# op_amp_brd.net
KiCad netlist of a schematic drawn in EAGLE
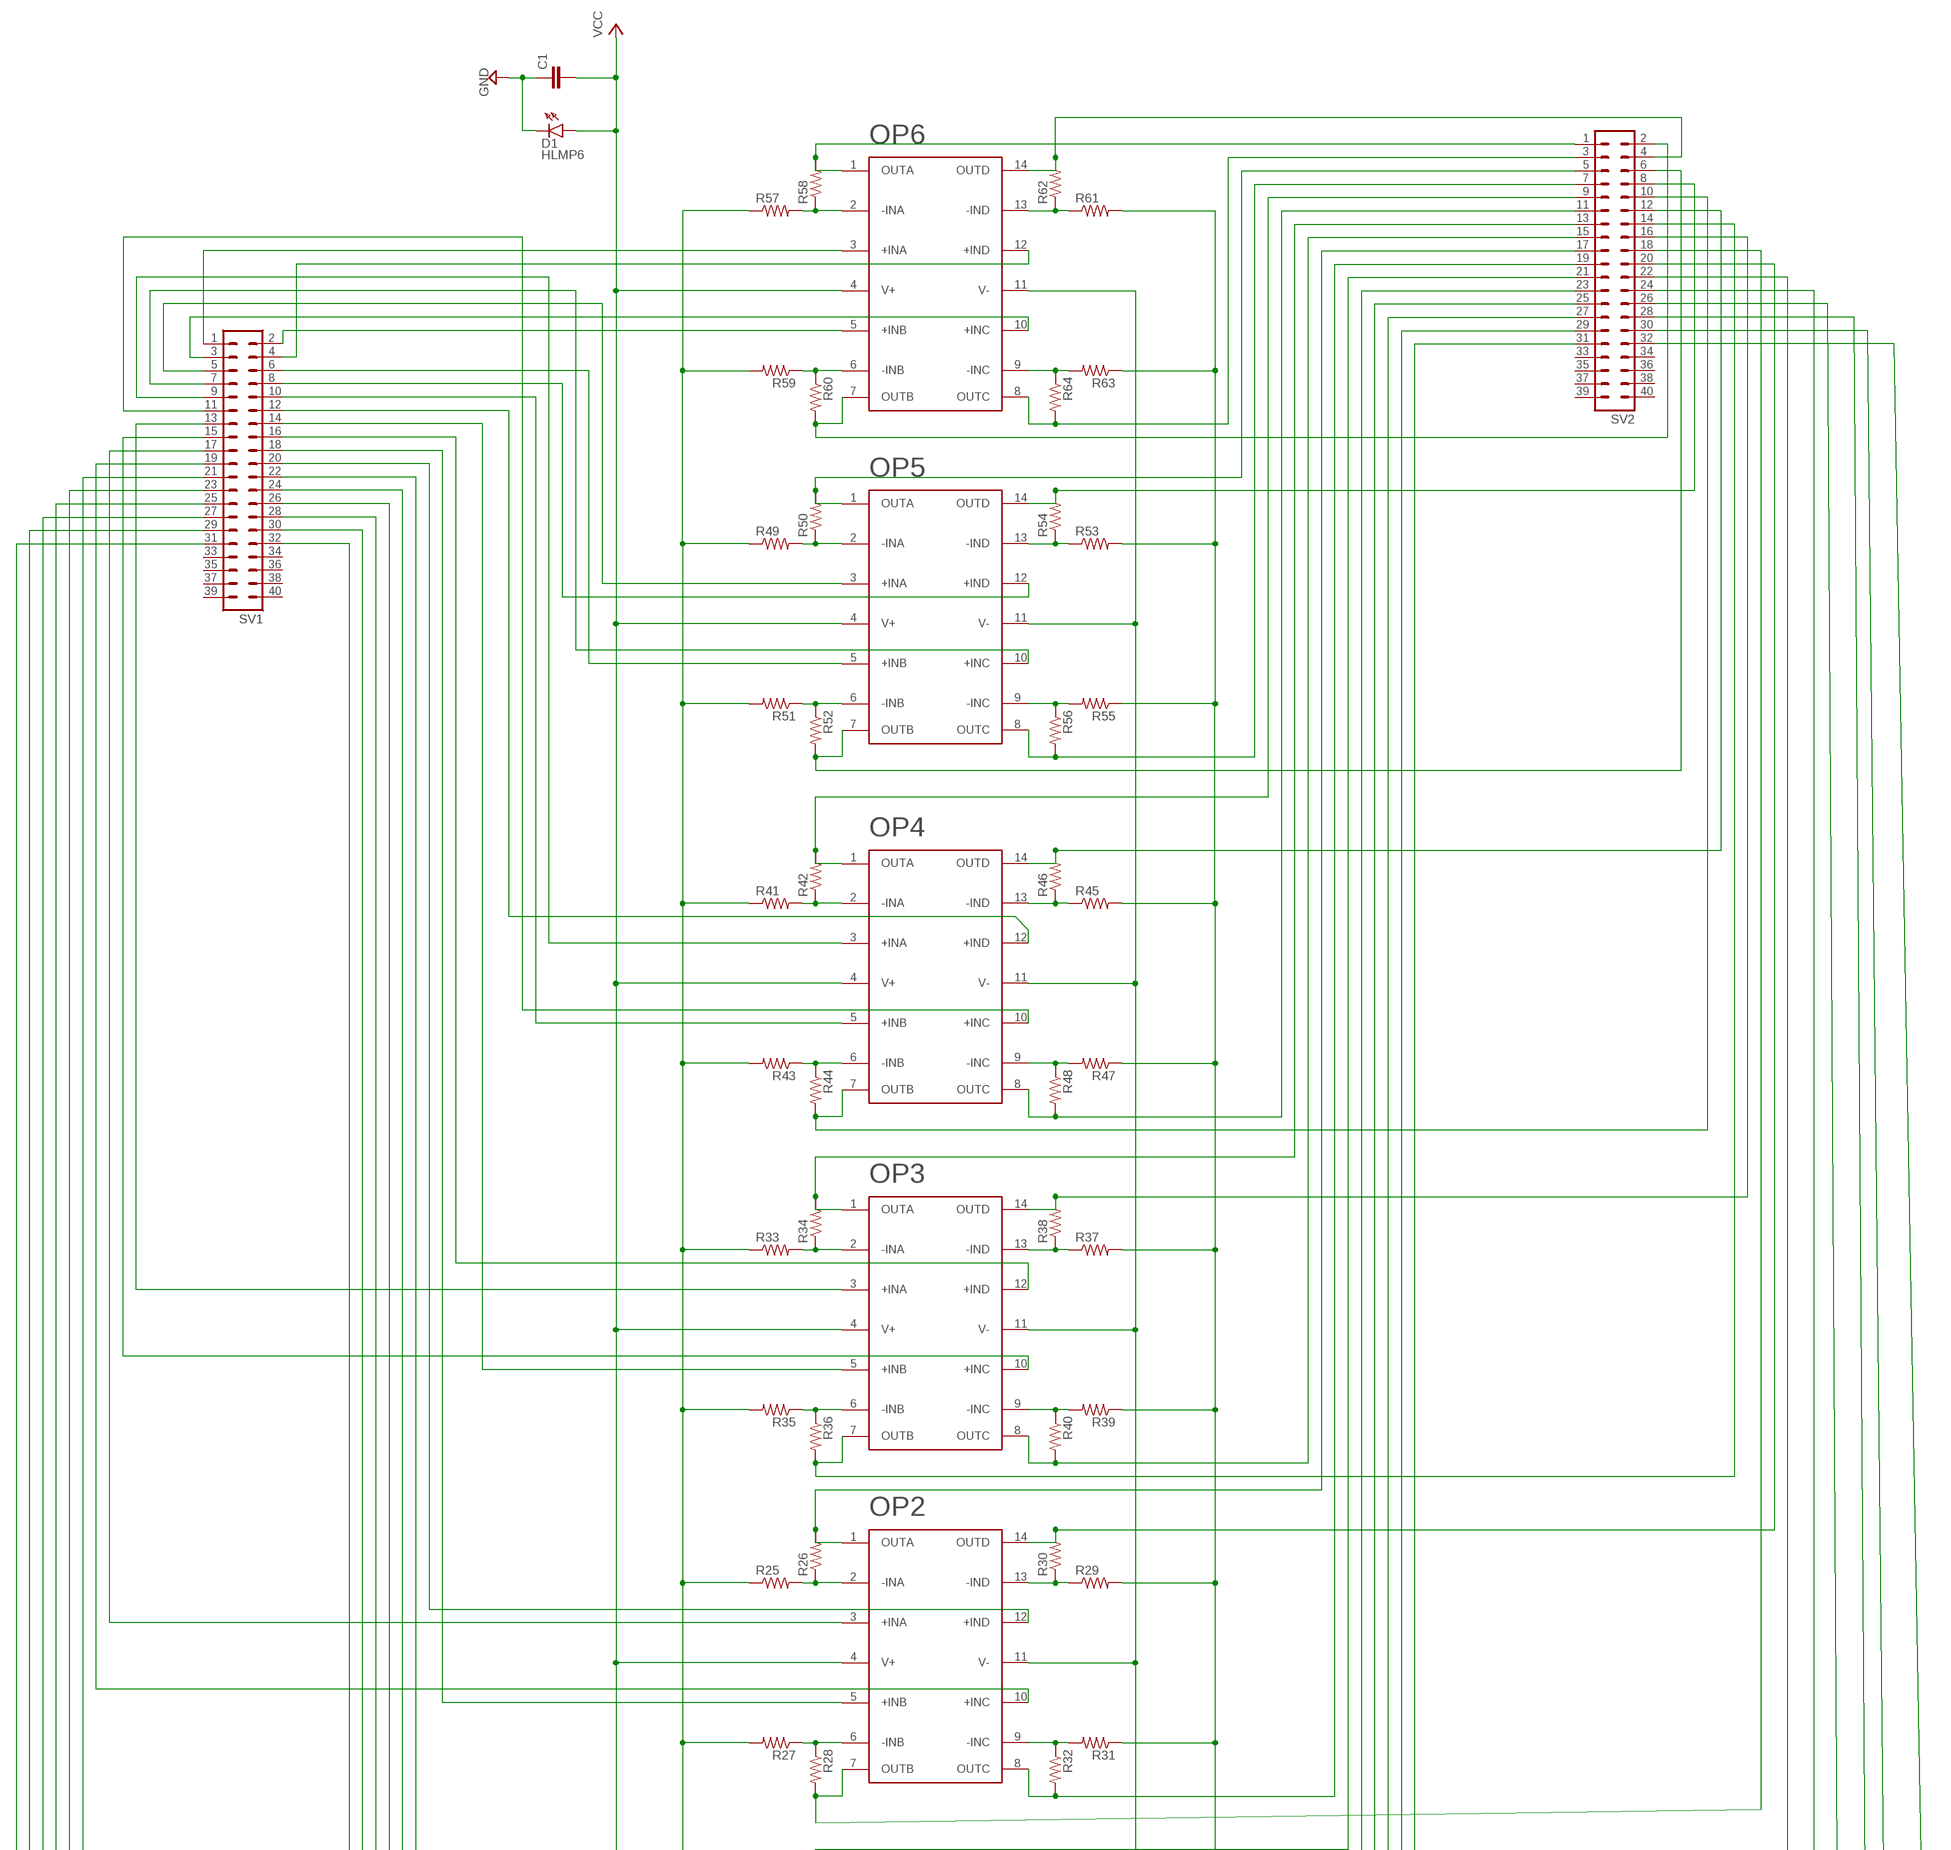
[diagram p0: schematic, sheet 1, part 1 of 2]
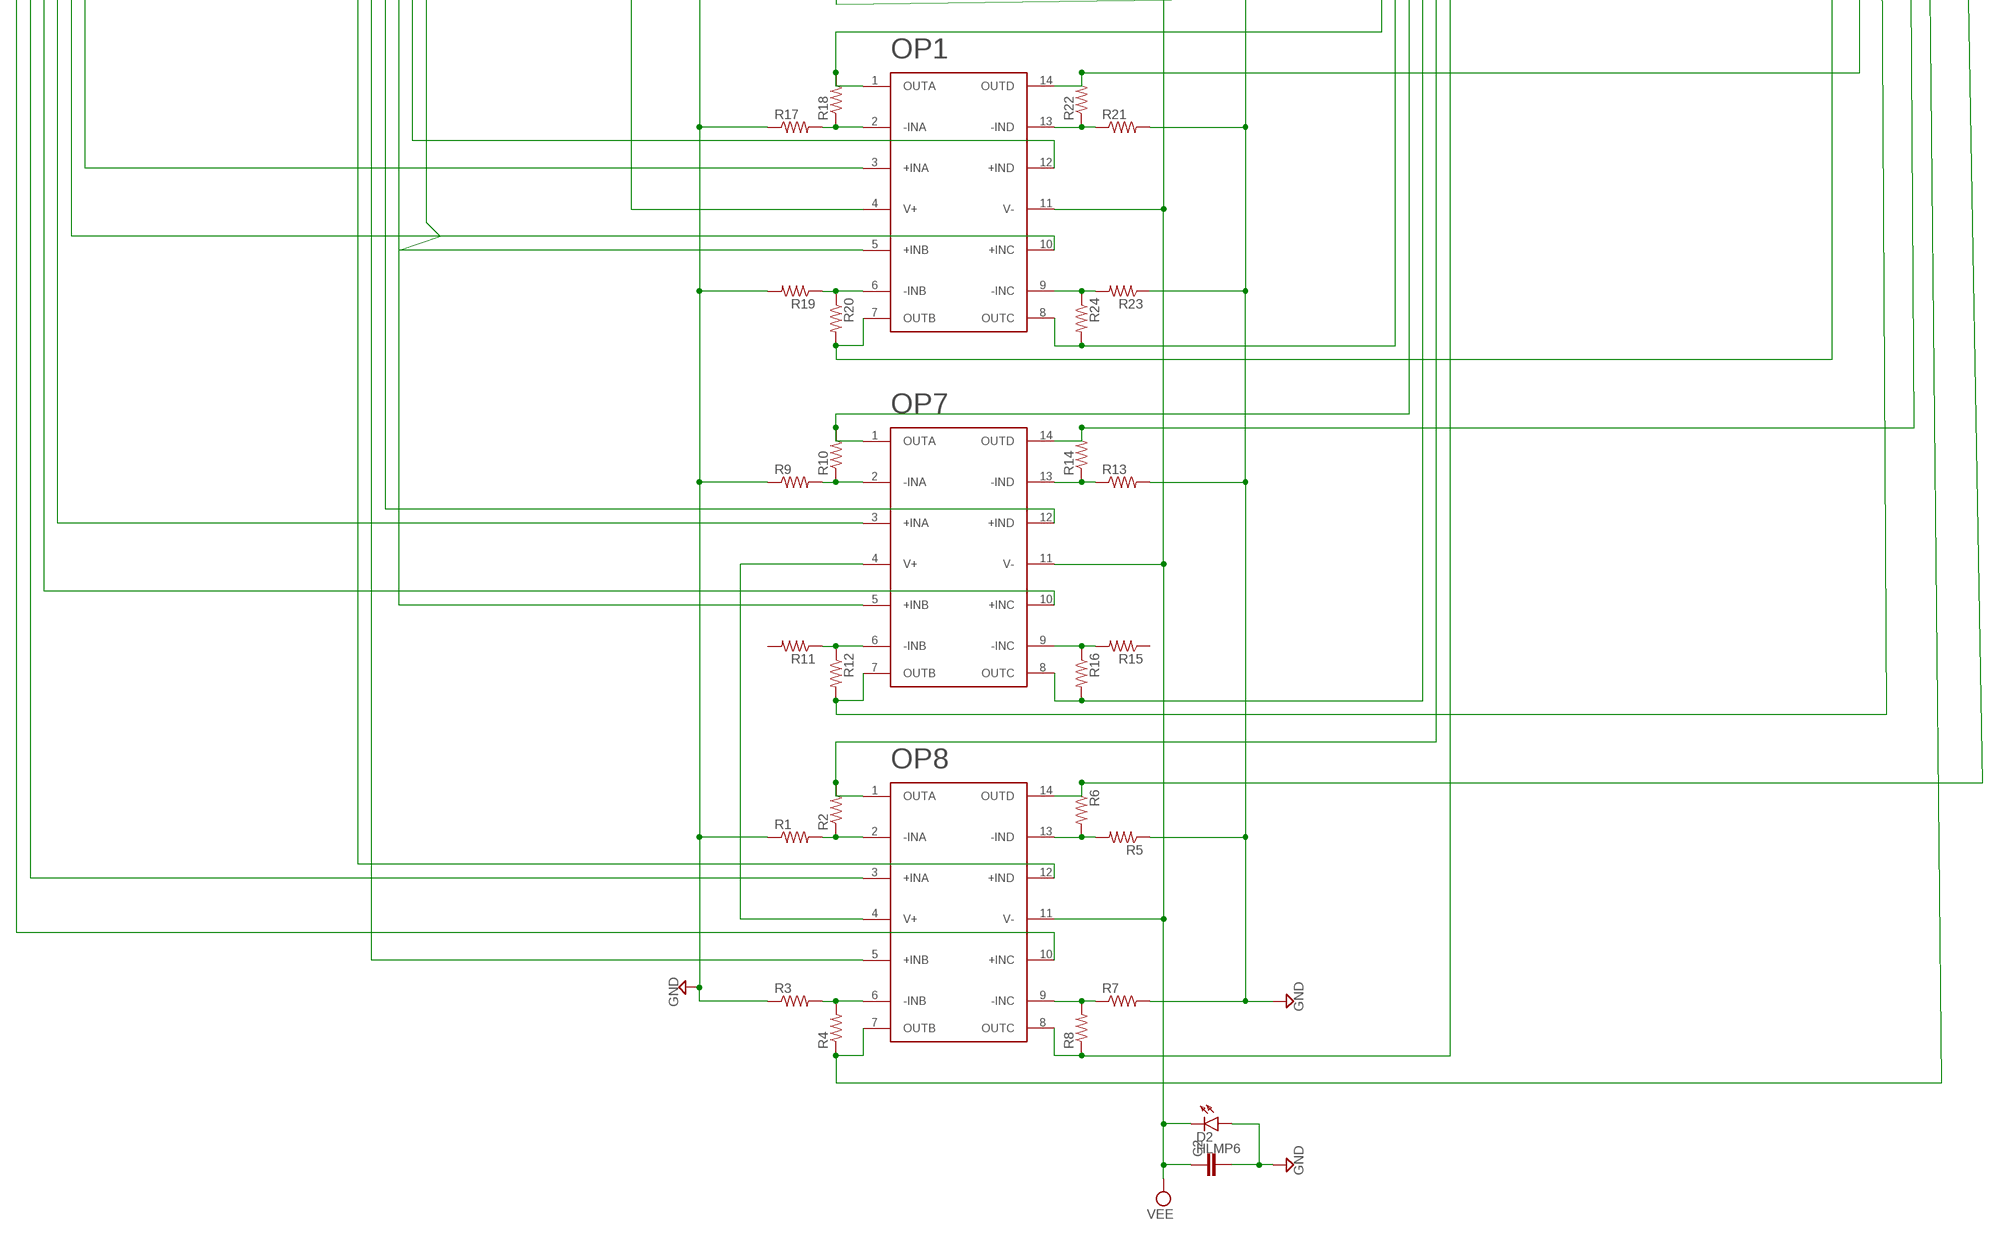
[diagram p1: schematic, sheet 1, part 2 of 2]

(export (version "E")
  (design (tool "Eeschema 10.0.6"))
  (components
    (comp (ref "C1")
      (value "C2,5-3")
      (footprint "eagle-import:C2.5-3")
      (libsource (lib "eagle-import") (part "C2,5-3"))
    )
    (comp (ref "C2")
      (value "C2,5-3")
      (footprint "eagle-import:C2.5-3")
      (libsource (lib "eagle-import") (part "C2,5-3"))
    )
    (comp (ref "D1")
      (value "HLMP6")
      (footprint "eagle-import:HLMP6")
      (fields (field (name "MF") "AGILENT TECHNOLOGIES") (field (name "MPN") "HLMP-6500"))
      (libsource (lib "eagle-import") (part "HLMP6"))
    )
    (comp (ref "D2")
      (value "HLMP6")
      (footprint "eagle-import:HLMP6")
      (fields (field (name "MF") "AGILENT TECHNOLOGIES") (field (name "MPN") "HLMP-6500"))
      (libsource (lib "eagle-import") (part "HLMP6"))
    )
    (comp (ref "OP1")
      (value "OPAX4172")
      (footprint "eagle-import:OPAX172")
      (libsource (lib "eagle-import") (part "OPAX4172"))
    )
    (comp (ref "OP2")
      (value "OPAX4172")
      (footprint "eagle-import:OPAX172")
      (libsource (lib "eagle-import") (part "OPAX4172"))
    )
    (comp (ref "OP3")
      (value "OPAX4172")
      (footprint "eagle-import:OPAX172")
      (libsource (lib "eagle-import") (part "OPAX4172"))
    )
    (comp (ref "OP4")
      (value "OPAX4172")
      (footprint "eagle-import:OPAX172")
      (libsource (lib "eagle-import") (part "OPAX4172"))
    )
    (comp (ref "OP5")
      (value "OPAX4172")
      (footprint "eagle-import:OPAX172")
      (libsource (lib "eagle-import") (part "OPAX4172"))
    )
    (comp (ref "OP6")
      (value "OPAX4172")
      (footprint "eagle-import:OPAX172")
      (libsource (lib "eagle-import") (part "OPAX4172"))
    )
    (comp (ref "OP7")
      (value "OPAX4172")
      (footprint "eagle-import:OPAX172")
      (libsource (lib "eagle-import") (part "OPAX4172"))
    )
    (comp (ref "OP8")
      (value "OPAX4172")
      (footprint "eagle-import:OPAX172")
      (libsource (lib "eagle-import") (part "OPAX4172"))
    )
    (comp (ref "R1")
      (value "R-US_0204/2V")
      (footprint "eagle-import:0204V")
      (libsource (lib "eagle-import") (part "R-US_0204/2V"))
    )
    (comp (ref "R2")
      (value "R-US_0204/2V")
      (footprint "eagle-import:0204V")
      (libsource (lib "eagle-import") (part "R-US_0204/2V"))
    )
    (comp (ref "R3")
      (value "R-US_0204/2V")
      (footprint "eagle-import:0204V")
      (libsource (lib "eagle-import") (part "R-US_0204/2V"))
    )
    (comp (ref "R4")
      (value "R-US_0204/2V")
      (footprint "eagle-import:0204V")
      (libsource (lib "eagle-import") (part "R-US_0204/2V"))
    )
    (comp (ref "R5")
      (value "R-US_0204/2V")
      (footprint "eagle-import:0204V")
      (libsource (lib "eagle-import") (part "R-US_0204/2V"))
    )
    (comp (ref "R6")
      (value "R-US_0204/2V")
      (footprint "eagle-import:0204V")
      (libsource (lib "eagle-import") (part "R-US_0204/2V"))
    )
    (comp (ref "R7")
      (value "R-US_0204/2V")
      (footprint "eagle-import:0204V")
      (libsource (lib "eagle-import") (part "R-US_0204/2V"))
    )
    (comp (ref "R8")
      (value "R-US_0204/2V")
      (footprint "eagle-import:0204V")
      (libsource (lib "eagle-import") (part "R-US_0204/2V"))
    )
    (comp (ref "R9")
      (value "R-US_0204/2V")
      (footprint "eagle-import:0204V")
      (libsource (lib "eagle-import") (part "R-US_0204/2V"))
    )
    (comp (ref "R10")
      (value "R-US_0204/2V")
      (footprint "eagle-import:0204V")
      (libsource (lib "eagle-import") (part "R-US_0204/2V"))
    )
    (comp (ref "R11")
      (value "R-US_0204/2V")
      (footprint "eagle-import:0204V")
      (libsource (lib "eagle-import") (part "R-US_0204/2V"))
    )
    (comp (ref "R12")
      (value "R-US_0204/2V")
      (footprint "eagle-import:0204V")
      (libsource (lib "eagle-import") (part "R-US_0204/2V"))
    )
    (comp (ref "R13")
      (value "R-US_0204/2V")
      (footprint "eagle-import:0204V")
      (libsource (lib "eagle-import") (part "R-US_0204/2V"))
    )
    (comp (ref "R14")
      (value "R-US_0204/2V")
      (footprint "eagle-import:0204V")
      (libsource (lib "eagle-import") (part "R-US_0204/2V"))
    )
    (comp (ref "R15")
      (value "R-US_0204/2V")
      (footprint "eagle-import:0204V")
      (libsource (lib "eagle-import") (part "R-US_0204/2V"))
    )
    (comp (ref "R16")
      (value "R-US_0204/2V")
      (footprint "eagle-import:0204V")
      (libsource (lib "eagle-import") (part "R-US_0204/2V"))
    )
    (comp (ref "R17")
      (value "R-US_0204/2V")
      (footprint "eagle-import:0204V")
      (libsource (lib "eagle-import") (part "R-US_0204/2V"))
    )
    (comp (ref "R18")
      (value "R-US_0204/2V")
      (footprint "eagle-import:0204V")
      (libsource (lib "eagle-import") (part "R-US_0204/2V"))
    )
    (comp (ref "R19")
      (value "R-US_0204/2V")
      (footprint "eagle-import:0204V")
      (libsource (lib "eagle-import") (part "R-US_0204/2V"))
    )
    (comp (ref "R20")
      (value "R-US_0204/2V")
      (footprint "eagle-import:0204V")
      (libsource (lib "eagle-import") (part "R-US_0204/2V"))
    )
    (comp (ref "R21")
      (value "R-US_0204/2V")
      (footprint "eagle-import:0204V")
      (libsource (lib "eagle-import") (part "R-US_0204/2V"))
    )
    (comp (ref "R22")
      (value "R-US_0204/2V")
      (footprint "eagle-import:0204V")
      (libsource (lib "eagle-import") (part "R-US_0204/2V"))
    )
    (comp (ref "R23")
      (value "R-US_0204/2V")
      (footprint "eagle-import:0204V")
      (libsource (lib "eagle-import") (part "R-US_0204/2V"))
    )
    (comp (ref "R24")
      (value "R-US_0204/2V")
      (footprint "eagle-import:0204V")
      (libsource (lib "eagle-import") (part "R-US_0204/2V"))
    )
    (comp (ref "R25")
      (value "R-US_0204/2V")
      (footprint "eagle-import:0204V")
      (libsource (lib "eagle-import") (part "R-US_0204/2V"))
    )
    (comp (ref "R26")
      (value "R-US_0204/2V")
      (footprint "eagle-import:0204V")
      (libsource (lib "eagle-import") (part "R-US_0204/2V"))
    )
    (comp (ref "R27")
      (value "R-US_0204/2V")
      (footprint "eagle-import:0204V")
      (libsource (lib "eagle-import") (part "R-US_0204/2V"))
    )
    (comp (ref "R28")
      (value "R-US_0204/2V")
      (footprint "eagle-import:0204V")
      (libsource (lib "eagle-import") (part "R-US_0204/2V"))
    )
    (comp (ref "R29")
      (value "R-US_0204/2V")
      (footprint "eagle-import:0204V")
      (libsource (lib "eagle-import") (part "R-US_0204/2V"))
    )
    (comp (ref "R30")
      (value "R-US_0204/2V")
      (footprint "eagle-import:0204V")
      (libsource (lib "eagle-import") (part "R-US_0204/2V"))
    )
    (comp (ref "R31")
      (value "R-US_0204/2V")
      (footprint "eagle-import:0204V")
      (libsource (lib "eagle-import") (part "R-US_0204/2V"))
    )
    (comp (ref "R32")
      (value "R-US_0204/2V")
      (footprint "eagle-import:0204V")
      (libsource (lib "eagle-import") (part "R-US_0204/2V"))
    )
    (comp (ref "R33")
      (value "R-US_0204/2V")
      (footprint "eagle-import:0204V")
      (libsource (lib "eagle-import") (part "R-US_0204/2V"))
    )
    (comp (ref "R34")
      (value "R-US_0204/2V")
      (footprint "eagle-import:0204V")
      (libsource (lib "eagle-import") (part "R-US_0204/2V"))
    )
    (comp (ref "R35")
      (value "R-US_0204/2V")
      (footprint "eagle-import:0204V")
      (libsource (lib "eagle-import") (part "R-US_0204/2V"))
    )
    (comp (ref "R36")
      (value "R-US_0204/2V")
      (footprint "eagle-import:0204V")
      (libsource (lib "eagle-import") (part "R-US_0204/2V"))
    )
    (comp (ref "R37")
      (value "R-US_0204/2V")
      (footprint "eagle-import:0204V")
      (libsource (lib "eagle-import") (part "R-US_0204/2V"))
    )
    (comp (ref "R38")
      (value "R-US_0204/2V")
      (footprint "eagle-import:0204V")
      (libsource (lib "eagle-import") (part "R-US_0204/2V"))
    )
    (comp (ref "R39")
      (value "R-US_0204/2V")
      (footprint "eagle-import:0204V")
      (libsource (lib "eagle-import") (part "R-US_0204/2V"))
    )
    (comp (ref "R40")
      (value "R-US_0204/2V")
      (footprint "eagle-import:0204V")
      (libsource (lib "eagle-import") (part "R-US_0204/2V"))
    )
    (comp (ref "R41")
      (value "R-US_0204/2V")
      (footprint "eagle-import:0204V")
      (libsource (lib "eagle-import") (part "R-US_0204/2V"))
    )
    (comp (ref "R42")
      (value "R-US_0204/2V")
      (footprint "eagle-import:0204V")
      (libsource (lib "eagle-import") (part "R-US_0204/2V"))
    )
    (comp (ref "R43")
      (value "R-US_0204/2V")
      (footprint "eagle-import:0204V")
      (libsource (lib "eagle-import") (part "R-US_0204/2V"))
    )
    (comp (ref "R44")
      (value "R-US_0204/2V")
      (footprint "eagle-import:0204V")
      (libsource (lib "eagle-import") (part "R-US_0204/2V"))
    )
    (comp (ref "R45")
      (value "R-US_0204/2V")
      (footprint "eagle-import:0204V")
      (libsource (lib "eagle-import") (part "R-US_0204/2V"))
    )
    (comp (ref "R46")
      (value "R-US_0204/2V")
      (footprint "eagle-import:0204V")
      (libsource (lib "eagle-import") (part "R-US_0204/2V"))
    )
    (comp (ref "R47")
      (value "R-US_0204/2V")
      (footprint "eagle-import:0204V")
      (libsource (lib "eagle-import") (part "R-US_0204/2V"))
    )
    (comp (ref "R48")
      (value "R-US_0204/2V")
      (footprint "eagle-import:0204V")
      (libsource (lib "eagle-import") (part "R-US_0204/2V"))
    )
    (comp (ref "R49")
      (value "R-US_0204/2V")
      (footprint "eagle-import:0204V")
      (libsource (lib "eagle-import") (part "R-US_0204/2V"))
    )
    (comp (ref "R50")
      (value "R-US_0204/2V")
      (footprint "eagle-import:0204V")
      (libsource (lib "eagle-import") (part "R-US_0204/2V"))
    )
    (comp (ref "R51")
      (value "R-US_0204/2V")
      (footprint "eagle-import:0204V")
      (libsource (lib "eagle-import") (part "R-US_0204/2V"))
    )
    (comp (ref "R52")
      (value "R-US_0204/2V")
      (footprint "eagle-import:0204V")
      (libsource (lib "eagle-import") (part "R-US_0204/2V"))
    )
    (comp (ref "R53")
      (value "R-US_0204/2V")
      (footprint "eagle-import:0204V")
      (libsource (lib "eagle-import") (part "R-US_0204/2V"))
    )
    (comp (ref "R54")
      (value "R-US_0204/2V")
      (footprint "eagle-import:0204V")
      (libsource (lib "eagle-import") (part "R-US_0204/2V"))
    )
    (comp (ref "R55")
      (value "R-US_0204/2V")
      (footprint "eagle-import:0204V")
      (libsource (lib "eagle-import") (part "R-US_0204/2V"))
    )
    (comp (ref "R56")
      (value "R-US_0204/2V")
      (footprint "eagle-import:0204V")
      (libsource (lib "eagle-import") (part "R-US_0204/2V"))
    )
    (comp (ref "R57")
      (value "R-US_0204/2V")
      (footprint "eagle-import:0204V")
      (libsource (lib "eagle-import") (part "R-US_0204/2V"))
    )
    (comp (ref "R58")
      (value "R-US_0204/2V")
      (footprint "eagle-import:0204V")
      (libsource (lib "eagle-import") (part "R-US_0204/2V"))
    )
    (comp (ref "R59")
      (value "R-US_0204/2V")
      (footprint "eagle-import:0204V")
      (libsource (lib "eagle-import") (part "R-US_0204/2V"))
    )
    (comp (ref "R60")
      (value "R-US_0204/2V")
      (footprint "eagle-import:0204V")
      (libsource (lib "eagle-import") (part "R-US_0204/2V"))
    )
    (comp (ref "R61")
      (value "R-US_0204/2V")
      (footprint "eagle-import:0204V")
      (libsource (lib "eagle-import") (part "R-US_0204/2V"))
    )
    (comp (ref "R62")
      (value "R-US_0204/2V")
      (footprint "eagle-import:0204V")
      (libsource (lib "eagle-import") (part "R-US_0204/2V"))
    )
    (comp (ref "R63")
      (value "R-US_0204/2V")
      (footprint "eagle-import:0204V")
      (libsource (lib "eagle-import") (part "R-US_0204/2V"))
    )
    (comp (ref "R64")
      (value "R-US_0204/2V")
      (footprint "eagle-import:0204V")
      (libsource (lib "eagle-import") (part "R-US_0204/2V"))
    )
    (comp (ref "SV1")
      (value "MA20-2")
      (footprint "eagle-import:MA20-2")
      (libsource (lib "eagle-import") (part "MA20-2"))
    )
    (comp (ref "SV2")
      (value "MA20-2W")
      (footprint "eagle-import:MA20-2W")
      (libsource (lib "eagle-import") (part "MA20-2W"))
    )
  )
  (nets
    (net (code "1") (name "GND") (class "Default")
      (node (ref "C1") (pin "1") (pinfunction "1_1") (pintype "passive"))
      (node (ref "C2") (pin "2") (pinfunction "2_2") (pintype "passive"))
      (node (ref "D1") (pin "K") (pinfunction "K_K") (pintype "passive"))
      (node (ref "D2") (pin "A") (pinfunction "A_A") (pintype "passive"))
      (node (ref "R1") (pin "1") (pinfunction "1_1") (pintype "passive"))
      (node (ref "R13") (pin "2") (pinfunction "2_2") (pintype "passive"))
      (node (ref "R17") (pin "1") (pinfunction "1_1") (pintype "passive"))
      (node (ref "R19") (pin "2") (pinfunction "2_2") (pintype "passive"))
      (node (ref "R21") (pin "2") (pinfunction "2_2") (pintype "passive"))
      (node (ref "R23") (pin "1") (pinfunction "1_1") (pintype "passive"))
      (node (ref "R25") (pin "1") (pinfunction "1_1") (pintype "passive"))
      (node (ref "R27") (pin "2") (pinfunction "2_2") (pintype "passive"))
      (node (ref "R29") (pin "2") (pinfunction "2_2") (pintype "passive"))
      (node (ref "R3") (pin "1") (pinfunction "1_1") (pintype "passive"))
      (node (ref "R31") (pin "1") (pinfunction "1_1") (pintype "passive"))
      (node (ref "R33") (pin "1") (pinfunction "1_1") (pintype "passive"))
      (node (ref "R35") (pin "2") (pinfunction "2_2") (pintype "passive"))
      (node (ref "R37") (pin "2") (pinfunction "2_2") (pintype "passive"))
      (node (ref "R39") (pin "1") (pinfunction "1_1") (pintype "passive"))
      (node (ref "R41") (pin "1") (pinfunction "1_1") (pintype "passive"))
      (node (ref "R43") (pin "2") (pinfunction "2_2") (pintype "passive"))
      (node (ref "R45") (pin "2") (pinfunction "2_2") (pintype "passive"))
      (node (ref "R47") (pin "1") (pinfunction "1_1") (pintype "passive"))
      (node (ref "R49") (pin "1") (pinfunction "1_1") (pintype "passive"))
      (node (ref "R5") (pin "1") (pinfunction "1_1") (pintype "passive"))
      (node (ref "R51") (pin "2") (pinfunction "2_2") (pintype "passive"))
      (node (ref "R53") (pin "2") (pinfunction "2_2") (pintype "passive"))
      (node (ref "R55") (pin "1") (pinfunction "1_1") (pintype "passive"))
      (node (ref "R57") (pin "1") (pinfunction "1_1") (pintype "passive"))
      (node (ref "R59") (pin "2") (pinfunction "2_2") (pintype "passive"))
      (node (ref "R61") (pin "2") (pinfunction "2_2") (pintype "passive"))
      (node (ref "R63") (pin "1") (pinfunction "1_1") (pintype "passive"))
      (node (ref "R7") (pin "2") (pinfunction "2_2") (pintype "passive"))
      (node (ref "R9") (pin "1") (pinfunction "1_1") (pintype "passive"))
    )
    (net (code "2") (name "Net-(OP1-+INA)") (class "Default")
      (node (ref "OP1") (pin "3") (pinfunction "+INA_3") (pintype "bidirectional"))
      (node (ref "SV1") (pin "21") (pinfunction "21_21") (pintype "passive"))
    )
    (net (code "3") (name "Net-(OP1-+INB)") (class "Default")
      (node (ref "OP1") (pin "5") (pinfunction "+INB_5") (pintype "bidirectional"))
      (node (ref "SV1") (pin "22") (pinfunction "22_22") (pintype "passive"))
    )
    (net (code "4") (name "Net-(OP1-+INC)") (class "Default")
      (node (ref "OP1") (pin "10") (pinfunction "+INC_10") (pintype "bidirectional"))
      (node (ref "SV1") (pin "23") (pinfunction "23_23") (pintype "passive"))
    )
    (net (code "5") (name "Net-(OP1-+IND)") (class "Default")
      (node (ref "OP1") (pin "12") (pinfunction "+IND_12") (pintype "bidirectional"))
      (node (ref "SV1") (pin "24") (pinfunction "24_24") (pintype "passive"))
    )
    (net (code "6") (name "Net-(OP1--INA)") (class "Default")
      (node (ref "OP1") (pin "2") (pinfunction "-INA_2") (pintype "bidirectional"))
      (node (ref "R17") (pin "2") (pinfunction "2_2") (pintype "passive"))
      (node (ref "R18") (pin "1") (pinfunction "1_1") (pintype "passive"))
    )
    (net (code "7") (name "Net-(OP1--INB)") (class "Default")
      (node (ref "OP1") (pin "6") (pinfunction "-INB_6") (pintype "bidirectional"))
      (node (ref "R19") (pin "1") (pinfunction "1_1") (pintype "passive"))
      (node (ref "R20") (pin "1") (pinfunction "1_1") (pintype "passive"))
    )
    (net (code "8") (name "Net-(OP1--INC)") (class "Default")
      (node (ref "OP1") (pin "9") (pinfunction "-INC_9") (pintype "bidirectional"))
      (node (ref "R23") (pin "2") (pinfunction "2_2") (pintype "passive"))
      (node (ref "R24") (pin "1") (pinfunction "1_1") (pintype "passive"))
    )
    (net (code "9") (name "Net-(OP1--IND)") (class "Default")
      (node (ref "OP1") (pin "13") (pinfunction "-IND_13") (pintype "bidirectional"))
      (node (ref "R21") (pin "1") (pinfunction "1_1") (pintype "passive"))
      (node (ref "R22") (pin "1") (pinfunction "1_1") (pintype "passive"))
    )
    (net (code "10") (name "Net-(OP1-OUTA)") (class "Default")
      (node (ref "OP1") (pin "1") (pinfunction "OUTA_1") (pintype "bidirectional"))
      (node (ref "R18") (pin "2") (pinfunction "2_2") (pintype "passive"))
      (node (ref "SV2") (pin "21") (pinfunction "21_21") (pintype "passive"))
    )
    (net (code "11") (name "Net-(OP1-OUTB)") (class "Default")
      (node (ref "OP1") (pin "7") (pinfunction "OUTB_7") (pintype "bidirectional"))
      (node (ref "R20") (pin "2") (pinfunction "2_2") (pintype "passive"))
      (node (ref "SV2") (pin "22") (pinfunction "22_22") (pintype "passive"))
    )
    (net (code "12") (name "Net-(OP1-OUTC)") (class "Default")
      (node (ref "OP1") (pin "8") (pinfunction "OUTC_8") (pintype "bidirectional"))
      (node (ref "R24") (pin "2") (pinfunction "2_2") (pintype "passive"))
      (node (ref "SV2") (pin "23") (pinfunction "23_23") (pintype "passive"))
    )
    (net (code "13") (name "Net-(OP1-OUTD)") (class "Default")
      (node (ref "OP1") (pin "14") (pinfunction "OUTD_14") (pintype "bidirectional"))
      (node (ref "R22") (pin "2") (pinfunction "2_2") (pintype "passive"))
      (node (ref "SV2") (pin "24") (pinfunction "24_24") (pintype "passive"))
    )
    (net (code "14") (name "Net-(OP2-+INA)") (class "Default")
      (node (ref "OP2") (pin "3") (pinfunction "+INA_3") (pintype "bidirectional"))
      (node (ref "SV1") (pin "17") (pinfunction "17_17") (pintype "passive"))
    )
    (net (code "15") (name "Net-(OP2-+INB)") (class "Default")
      (node (ref "OP2") (pin "5") (pinfunction "+INB_5") (pintype "bidirectional"))
      (node (ref "SV1") (pin "18") (pinfunction "18_18") (pintype "passive"))
    )
    (net (code "16") (name "Net-(OP2-+INC)") (class "Default")
      (node (ref "OP2") (pin "10") (pinfunction "+INC_10") (pintype "bidirectional"))
      (node (ref "SV1") (pin "19") (pinfunction "19_19") (pintype "passive"))
    )
    (net (code "17") (name "Net-(OP2-+IND)") (class "Default")
      (node (ref "OP2") (pin "12") (pinfunction "+IND_12") (pintype "bidirectional"))
      (node (ref "SV1") (pin "20") (pinfunction "20_20") (pintype "passive"))
    )
    (net (code "18") (name "Net-(OP2--INA)") (class "Default")
      (node (ref "OP2") (pin "2") (pinfunction "-INA_2") (pintype "bidirectional"))
      (node (ref "R25") (pin "2") (pinfunction "2_2") (pintype "passive"))
      (node (ref "R26") (pin "1") (pinfunction "1_1") (pintype "passive"))
    )
    (net (code "19") (name "Net-(OP2--INB)") (class "Default")
      (node (ref "OP2") (pin "6") (pinfunction "-INB_6") (pintype "bidirectional"))
      (node (ref "R27") (pin "1") (pinfunction "1_1") (pintype "passive"))
      (node (ref "R28") (pin "1") (pinfunction "1_1") (pintype "passive"))
    )
    (net (code "20") (name "Net-(OP2--INC)") (class "Default")
      (node (ref "OP2") (pin "9") (pinfunction "-INC_9") (pintype "bidirectional"))
      (node (ref "R31") (pin "2") (pinfunction "2_2") (pintype "passive"))
      (node (ref "R32") (pin "1") (pinfunction "1_1") (pintype "passive"))
    )
    (net (code "21") (name "Net-(OP2--IND)") (class "Default")
      (node (ref "OP2") (pin "13") (pinfunction "-IND_13") (pintype "bidirectional"))
      (node (ref "R29") (pin "1") (pinfunction "1_1") (pintype "passive"))
      (node (ref "R30") (pin "1") (pinfunction "1_1") (pintype "passive"))
    )
    (net (code "22") (name "Net-(OP2-OUTA)") (class "Default")
      (node (ref "OP2") (pin "1") (pinfunction "OUTA_1") (pintype "bidirectional"))
      (node (ref "R26") (pin "2") (pinfunction "2_2") (pintype "passive"))
      (node (ref "SV2") (pin "17") (pinfunction "17_17") (pintype "passive"))
    )
    (net (code "23") (name "Net-(OP2-OUTB)") (class "Default")
      (node (ref "OP2") (pin "7") (pinfunction "OUTB_7") (pintype "bidirectional"))
      (node (ref "R28") (pin "2") (pinfunction "2_2") (pintype "passive"))
      (node (ref "SV2") (pin "18") (pinfunction "18_18") (pintype "passive"))
    )
    (net (code "24") (name "Net-(OP2-OUTC)") (class "Default")
      (node (ref "OP2") (pin "8") (pinfunction "OUTC_8") (pintype "bidirectional"))
      (node (ref "R32") (pin "2") (pinfunction "2_2") (pintype "passive"))
      (node (ref "SV2") (pin "19") (pinfunction "19_19") (pintype "passive"))
    )
    (net (code "25") (name "Net-(OP2-OUTD)") (class "Default")
      (node (ref "OP2") (pin "14") (pinfunction "OUTD_14") (pintype "bidirectional"))
      (node (ref "R30") (pin "2") (pinfunction "2_2") (pintype "passive"))
      (node (ref "SV2") (pin "20") (pinfunction "20_20") (pintype "passive"))
    )
    (net (code "26") (name "Net-(OP3-+INA)") (class "Default")
      (node (ref "OP3") (pin "3") (pinfunction "+INA_3") (pintype "bidirectional"))
      (node (ref "SV1") (pin "13") (pinfunction "13_13") (pintype "passive"))
    )
    (net (code "27") (name "Net-(OP3-+INB)") (class "Default")
      (node (ref "OP3") (pin "5") (pinfunction "+INB_5") (pintype "bidirectional"))
      (node (ref "SV1") (pin "14") (pinfunction "14_14") (pintype "passive"))
    )
    (net (code "28") (name "Net-(OP3-+INC)") (class "Default")
      (node (ref "OP3") (pin "10") (pinfunction "+INC_10") (pintype "bidirectional"))
      (node (ref "SV1") (pin "15") (pinfunction "15_15") (pintype "passive"))
    )
    (net (code "29") (name "Net-(OP3-+IND)") (class "Default")
      (node (ref "OP3") (pin "12") (pinfunction "+IND_12") (pintype "bidirectional"))
      (node (ref "SV1") (pin "16") (pinfunction "16_16") (pintype "passive"))
    )
    (net (code "30") (name "Net-(OP3--INA)") (class "Default")
      (node (ref "OP3") (pin "2") (pinfunction "-INA_2") (pintype "bidirectional"))
      (node (ref "R33") (pin "2") (pinfunction "2_2") (pintype "passive"))
      (node (ref "R34") (pin "1") (pinfunction "1_1") (pintype "passive"))
    )
    (net (code "31") (name "Net-(OP3--INB)") (class "Default")
      (node (ref "OP3") (pin "6") (pinfunction "-INB_6") (pintype "bidirectional"))
      (node (ref "R35") (pin "1") (pinfunction "1_1") (pintype "passive"))
      (node (ref "R36") (pin "1") (pinfunction "1_1") (pintype "passive"))
    )
    (net (code "32") (name "Net-(OP3--INC)") (class "Default")
      (node (ref "OP3") (pin "9") (pinfunction "-INC_9") (pintype "bidirectional"))
      (node (ref "R39") (pin "2") (pinfunction "2_2") (pintype "passive"))
      (node (ref "R40") (pin "1") (pinfunction "1_1") (pintype "passive"))
    )
    (net (code "33") (name "Net-(OP3--IND)") (class "Default")
      (node (ref "OP3") (pin "13") (pinfunction "-IND_13") (pintype "bidirectional"))
      (node (ref "R37") (pin "1") (pinfunction "1_1") (pintype "passive"))
      (node (ref "R38") (pin "1") (pinfunction "1_1") (pintype "passive"))
    )
    (net (code "34") (name "Net-(OP3-OUTA)") (class "Default")
      (node (ref "OP3") (pin "1") (pinfunction "OUTA_1") (pintype "bidirectional"))
      (node (ref "R34") (pin "2") (pinfunction "2_2") (pintype "passive"))
      (node (ref "SV2") (pin "13") (pinfunction "13_13") (pintype "passive"))
    )
    (net (code "35") (name "Net-(OP3-OUTB)") (class "Default")
      (node (ref "OP3") (pin "7") (pinfunction "OUTB_7") (pintype "bidirectional"))
      (node (ref "R36") (pin "2") (pinfunction "2_2") (pintype "passive"))
      (node (ref "SV2") (pin "14") (pinfunction "14_14") (pintype "passive"))
    )
    (net (code "36") (name "Net-(OP3-OUTC)") (class "Default")
      (node (ref "OP3") (pin "8") (pinfunction "OUTC_8") (pintype "bidirectional"))
      (node (ref "R40") (pin "2") (pinfunction "2_2") (pintype "passive"))
      (node (ref "SV2") (pin "15") (pinfunction "15_15") (pintype "passive"))
    )
    (net (code "37") (name "Net-(OP3-OUTD)") (class "Default")
      (node (ref "OP3") (pin "14") (pinfunction "OUTD_14") (pintype "bidirectional"))
      (node (ref "R38") (pin "2") (pinfunction "2_2") (pintype "passive"))
      (node (ref "SV2") (pin "16") (pinfunction "16_16") (pintype "passive"))
    )
    (net (code "38") (name "Net-(OP4-+INA)") (class "Default")
      (node (ref "OP4") (pin "3") (pinfunction "+INA_3") (pintype "bidirectional"))
      (node (ref "SV1") (pin "9") (pinfunction "9_9") (pintype "passive"))
    )
    (net (code "39") (name "Net-(OP4-+INB)") (class "Default")
      (node (ref "OP4") (pin "5") (pinfunction "+INB_5") (pintype "bidirectional"))
      (node (ref "SV1") (pin "10") (pinfunction "10_10") (pintype "passive"))
    )
    (net (code "40") (name "Net-(OP4-+INC)") (class "Default")
      (node (ref "OP4") (pin "10") (pinfunction "+INC_10") (pintype "bidirectional"))
      (node (ref "SV1") (pin "11") (pinfunction "11_11") (pintype "passive"))
    )
    (net (code "41") (name "Net-(OP4-+IND)") (class "Default")
      (node (ref "OP4") (pin "12") (pinfunction "+IND_12") (pintype "bidirectional"))
      (node (ref "SV1") (pin "12") (pinfunction "12_12") (pintype "passive"))
    )
    (net (code "42") (name "Net-(OP4--INA)") (class "Default")
      (node (ref "OP4") (pin "2") (pinfunction "-INA_2") (pintype "bidirectional"))
      (node (ref "R41") (pin "2") (pinfunction "2_2") (pintype "passive"))
      (node (ref "R42") (pin "1") (pinfunction "1_1") (pintype "passive"))
    )
    (net (code "43") (name "Net-(OP4--INB)") (class "Default")
      (node (ref "OP4") (pin "6") (pinfunction "-INB_6") (pintype "bidirectional"))
      (node (ref "R43") (pin "1") (pinfunction "1_1") (pintype "passive"))
      (node (ref "R44") (pin "1") (pinfunction "1_1") (pintype "passive"))
    )
    (net (code "44") (name "Net-(OP4--INC)") (class "Default")
      (node (ref "OP4") (pin "9") (pinfunction "-INC_9") (pintype "bidirectional"))
      (node (ref "R47") (pin "2") (pinfunction "2_2") (pintype "passive"))
      (node (ref "R48") (pin "1") (pinfunction "1_1") (pintype "passive"))
    )
    (net (code "45") (name "Net-(OP4--IND)") (class "Default")
      (node (ref "OP4") (pin "13") (pinfunction "-IND_13") (pintype "bidirectional"))
      (node (ref "R45") (pin "1") (pinfunction "1_1") (pintype "passive"))
      (node (ref "R46") (pin "1") (pinfunction "1_1") (pintype "passive"))
    )
    (net (code "46") (name "Net-(OP4-OUTA)") (class "Default")
      (node (ref "OP4") (pin "1") (pinfunction "OUTA_1") (pintype "bidirectional"))
      (node (ref "R42") (pin "2") (pinfunction "2_2") (pintype "passive"))
      (node (ref "SV2") (pin "9") (pinfunction "9_9") (pintype "passive"))
    )
    (net (code "47") (name "Net-(OP4-OUTB)") (class "Default")
      (node (ref "OP4") (pin "7") (pinfunction "OUTB_7") (pintype "bidirectional"))
      (node (ref "R44") (pin "2") (pinfunction "2_2") (pintype "passive"))
      (node (ref "SV2") (pin "10") (pinfunction "10_10") (pintype "passive"))
    )
    (net (code "48") (name "Net-(OP4-OUTC)") (class "Default")
      (node (ref "OP4") (pin "8") (pinfunction "OUTC_8") (pintype "bidirectional"))
      (node (ref "R48") (pin "2") (pinfunction "2_2") (pintype "passive"))
      (node (ref "SV2") (pin "11") (pinfunction "11_11") (pintype "passive"))
    )
    (net (code "49") (name "Net-(OP4-OUTD)") (class "Default")
      (node (ref "OP4") (pin "14") (pinfunction "OUTD_14") (pintype "bidirectional"))
      (node (ref "R46") (pin "2") (pinfunction "2_2") (pintype "passive"))
      (node (ref "SV2") (pin "12") (pinfunction "12_12") (pintype "passive"))
    )
    (net (code "50") (name "Net-(OP5-+INA)") (class "Default")
      (node (ref "OP5") (pin "3") (pinfunction "+INA_3") (pintype "bidirectional"))
      (node (ref "SV1") (pin "5") (pinfunction "5_5") (pintype "passive"))
    )
    (net (code "51") (name "Net-(OP5-+INB)") (class "Default")
      (node (ref "OP5") (pin "5") (pinfunction "+INB_5") (pintype "bidirectional"))
      (node (ref "SV1") (pin "6") (pinfunction "6_6") (pintype "passive"))
    )
    (net (code "52") (name "Net-(OP5-+INC)") (class "Default")
      (node (ref "OP5") (pin "10") (pinfunction "+INC_10") (pintype "bidirectional"))
      (node (ref "SV1") (pin "7") (pinfunction "7_7") (pintype "passive"))
    )
    (net (code "53") (name "Net-(OP5-+IND)") (class "Default")
      (node (ref "OP5") (pin "12") (pinfunction "+IND_12") (pintype "bidirectional"))
      (node (ref "SV1") (pin "8") (pinfunction "8_8") (pintype "passive"))
    )
    (net (code "54") (name "Net-(OP5--INA)") (class "Default")
      (node (ref "OP5") (pin "2") (pinfunction "-INA_2") (pintype "bidirectional"))
      (node (ref "R49") (pin "2") (pinfunction "2_2") (pintype "passive"))
      (node (ref "R50") (pin "1") (pinfunction "1_1") (pintype "passive"))
    )
    (net (code "55") (name "Net-(OP5--INB)") (class "Default")
      (node (ref "OP5") (pin "6") (pinfunction "-INB_6") (pintype "bidirectional"))
      (node (ref "R51") (pin "1") (pinfunction "1_1") (pintype "passive"))
      (node (ref "R52") (pin "1") (pinfunction "1_1") (pintype "passive"))
    )
    (net (code "56") (name "Net-(OP5--INC)") (class "Default")
      (node (ref "OP5") (pin "9") (pinfunction "-INC_9") (pintype "bidirectional"))
      (node (ref "R55") (pin "2") (pinfunction "2_2") (pintype "passive"))
      (node (ref "R56") (pin "1") (pinfunction "1_1") (pintype "passive"))
    )
    (net (code "57") (name "Net-(OP5--IND)") (class "Default")
      (node (ref "OP5") (pin "13") (pinfunction "-IND_13") (pintype "bidirectional"))
      (node (ref "R53") (pin "1") (pinfunction "1_1") (pintype "passive"))
      (node (ref "R54") (pin "1") (pinfunction "1_1") (pintype "passive"))
    )
    (net (code "58") (name "Net-(OP5-OUTA)") (class "Default")
      (node (ref "OP5") (pin "1") (pinfunction "OUTA_1") (pintype "bidirectional"))
      (node (ref "R50") (pin "2") (pinfunction "2_2") (pintype "passive"))
      (node (ref "SV2") (pin "5") (pinfunction "5_5") (pintype "passive"))
    )
    (net (code "59") (name "Net-(OP5-OUTB)") (class "Default")
      (node (ref "OP5") (pin "7") (pinfunction "OUTB_7") (pintype "bidirectional"))
      (node (ref "R52") (pin "2") (pinfunction "2_2") (pintype "passive"))
      (node (ref "SV2") (pin "6") (pinfunction "6_6") (pintype "passive"))
    )
    (net (code "60") (name "Net-(OP5-OUTC)") (class "Default")
      (node (ref "OP5") (pin "8") (pinfunction "OUTC_8") (pintype "bidirectional"))
      (node (ref "R56") (pin "2") (pinfunction "2_2") (pintype "passive"))
      (node (ref "SV2") (pin "7") (pinfunction "7_7") (pintype "passive"))
    )
    (net (code "61") (name "Net-(OP5-OUTD)") (class "Default")
      (node (ref "OP5") (pin "14") (pinfunction "OUTD_14") (pintype "bidirectional"))
      (node (ref "R54") (pin "2") (pinfunction "2_2") (pintype "passive"))
      (node (ref "SV2") (pin "8") (pinfunction "8_8") (pintype "passive"))
    )
    (net (code "62") (name "Net-(OP6-+INA)") (class "Default")
      (node (ref "OP6") (pin "3") (pinfunction "+INA_3") (pintype "bidirectional"))
      (node (ref "SV1") (pin "1") (pinfunction "1_1") (pintype "passive"))
    )
    (net (code "63") (name "Net-(OP6-+INB)") (class "Default")
      (node (ref "OP6") (pin "5") (pinfunction "+INB_5") (pintype "bidirectional"))
      (node (ref "SV1") (pin "2") (pinfunction "2_2") (pintype "passive"))
    )
    (net (code "64") (name "Net-(OP6-+INC)") (class "Default")
      (node (ref "OP6") (pin "10") (pinfunction "+INC_10") (pintype "bidirectional"))
      (node (ref "SV1") (pin "3") (pinfunction "3_3") (pintype "passive"))
    )
    (net (code "65") (name "Net-(OP6-+IND)") (class "Default")
      (node (ref "OP6") (pin "12") (pinfunction "+IND_12") (pintype "bidirectional"))
      (node (ref "SV1") (pin "4") (pinfunction "4_4") (pintype "passive"))
    )
    (net (code "66") (name "Net-(OP6--INA)") (class "Default")
      (node (ref "OP6") (pin "2") (pinfunction "-INA_2") (pintype "bidirectional"))
      (node (ref "R57") (pin "2") (pinfunction "2_2") (pintype "passive"))
      (node (ref "R58") (pin "1") (pinfunction "1_1") (pintype "passive"))
    )
    (net (code "67") (name "Net-(OP6--INB)") (class "Default")
      (node (ref "OP6") (pin "6") (pinfunction "-INB_6") (pintype "bidirectional"))
      (node (ref "R59") (pin "1") (pinfunction "1_1") (pintype "passive"))
      (node (ref "R60") (pin "1") (pinfunction "1_1") (pintype "passive"))
    )
    (net (code "68") (name "Net-(OP6--INC)") (class "Default")
      (node (ref "OP6") (pin "9") (pinfunction "-INC_9") (pintype "bidirectional"))
      (node (ref "R63") (pin "2") (pinfunction "2_2") (pintype "passive"))
      (node (ref "R64") (pin "1") (pinfunction "1_1") (pintype "passive"))
    )
    (net (code "69") (name "Net-(OP6--IND)") (class "Default")
      (node (ref "OP6") (pin "13") (pinfunction "-IND_13") (pintype "bidirectional"))
      (node (ref "R61") (pin "1") (pinfunction "1_1") (pintype "passive"))
      (node (ref "R62") (pin "1") (pinfunction "1_1") (pintype "passive"))
    )
    (net (code "70") (name "Net-(OP6-OUTA)") (class "Default")
      (node (ref "OP6") (pin "1") (pinfunction "OUTA_1") (pintype "bidirectional"))
      (node (ref "R58") (pin "2") (pinfunction "2_2") (pintype "passive"))
      (node (ref "SV2") (pin "1") (pinfunction "1_1") (pintype "passive"))
    )
    (net (code "71") (name "Net-(OP6-OUTB)") (class "Default")
      (node (ref "OP6") (pin "7") (pinfunction "OUTB_7") (pintype "bidirectional"))
      (node (ref "R60") (pin "2") (pinfunction "2_2") (pintype "passive"))
      (node (ref "SV2") (pin "2") (pinfunction "2_2") (pintype "passive"))
    )
    (net (code "72") (name "Net-(OP6-OUTC)") (class "Default")
      (node (ref "OP6") (pin "8") (pinfunction "OUTC_8") (pintype "bidirectional"))
      (node (ref "R64") (pin "2") (pinfunction "2_2") (pintype "passive"))
      (node (ref "SV2") (pin "3") (pinfunction "3_3") (pintype "passive"))
    )
    (net (code "73") (name "Net-(OP6-OUTD)") (class "Default")
      (node (ref "OP6") (pin "14") (pinfunction "OUTD_14") (pintype "bidirectional"))
      (node (ref "R62") (pin "2") (pinfunction "2_2") (pintype "passive"))
      (node (ref "SV2") (pin "4") (pinfunction "4_4") (pintype "passive"))
    )
    (net (code "74") (name "Net-(OP7-+INA)") (class "Default")
      (node (ref "OP7") (pin "3") (pinfunction "+INA_3") (pintype "bidirectional"))
      (node (ref "SV1") (pin "25") (pinfunction "25_25") (pintype "passive"))
    )
    (net (code "75") (name "Net-(OP7-+INB)") (class "Default")
      (node (ref "OP7") (pin "5") (pinfunction "+INB_5") (pintype "bidirectional"))
      (node (ref "SV1") (pin "26") (pinfunction "26_26") (pintype "passive"))
    )
    (net (code "76") (name "Net-(OP7-+INC)") (class "Default")
      (node (ref "OP7") (pin "10") (pinfunction "+INC_10") (pintype "bidirectional"))
      (node (ref "SV1") (pin "27") (pinfunction "27_27") (pintype "passive"))
    )
    (net (code "77") (name "Net-(OP7-+IND)") (class "Default")
      (node (ref "OP7") (pin "12") (pinfunction "+IND_12") (pintype "bidirectional"))
      (node (ref "SV1") (pin "28") (pinfunction "28_28") (pintype "passive"))
    )
    (net (code "78") (name "Net-(OP7--INA)") (class "Default")
      (node (ref "OP7") (pin "2") (pinfunction "-INA_2") (pintype "bidirectional"))
      (node (ref "R10") (pin "1") (pinfunction "1_1") (pintype "passive"))
      (node (ref "R9") (pin "2") (pinfunction "2_2") (pintype "passive"))
    )
    (net (code "79") (name "Net-(OP7--INB)") (class "Default")
      (node (ref "OP7") (pin "6") (pinfunction "-INB_6") (pintype "bidirectional"))
      (node (ref "R11") (pin "1") (pinfunction "1_1") (pintype "passive"))
      (node (ref "R12") (pin "1") (pinfunction "1_1") (pintype "passive"))
    )
    (net (code "80") (name "Net-(OP7--INC)") (class "Default")
      (node (ref "OP7") (pin "9") (pinfunction "-INC_9") (pintype "bidirectional"))
      (node (ref "R15") (pin "2") (pinfunction "2_2") (pintype "passive"))
      (node (ref "R16") (pin "1") (pinfunction "1_1") (pintype "passive"))
    )
    (net (code "81") (name "Net-(OP7--IND)") (class "Default")
      (node (ref "OP7") (pin "13") (pinfunction "-IND_13") (pintype "bidirectional"))
      (node (ref "R13") (pin "1") (pinfunction "1_1") (pintype "passive"))
      (node (ref "R14") (pin "1") (pinfunction "1_1") (pintype "passive"))
    )
    (net (code "82") (name "Net-(OP7-OUTA)") (class "Default")
      (node (ref "OP7") (pin "1") (pinfunction "OUTA_1") (pintype "bidirectional"))
      (node (ref "R10") (pin "2") (pinfunction "2_2") (pintype "passive"))
      (node (ref "SV2") (pin "25") (pinfunction "25_25") (pintype "passive"))
    )
    (net (code "83") (name "Net-(OP7-OUTB)") (class "Default")
      (node (ref "OP7") (pin "7") (pinfunction "OUTB_7") (pintype "bidirectional"))
      (node (ref "R12") (pin "2") (pinfunction "2_2") (pintype "passive"))
      (node (ref "SV2") (pin "26") (pinfunction "26_26") (pintype "passive"))
    )
    (net (code "84") (name "Net-(OP7-OUTC)") (class "Default")
      (node (ref "OP7") (pin "8") (pinfunction "OUTC_8") (pintype "bidirectional"))
      (node (ref "R16") (pin "2") (pinfunction "2_2") (pintype "passive"))
      (node (ref "SV2") (pin "27") (pinfunction "27_27") (pintype "passive"))
    )
    (net (code "85") (name "Net-(OP7-OUTD)") (class "Default")
      (node (ref "OP7") (pin "14") (pinfunction "OUTD_14") (pintype "bidirectional"))
      (node (ref "R14") (pin "2") (pinfunction "2_2") (pintype "passive"))
      (node (ref "SV2") (pin "28") (pinfunction "28_28") (pintype "passive"))
    )
    (net (code "86") (name "Net-(OP7-V+)") (class "Default")
      (node (ref "OP7") (pin "4") (pinfunction "V+_4") (pintype "bidirectional"))
      (node (ref "OP8") (pin "4") (pinfunction "V+_4") (pintype "bidirectional"))
    )
    (net (code "87") (name "Net-(OP8-+INA)") (class "Default")
      (node (ref "OP8") (pin "3") (pinfunction "+INA_3") (pintype "bidirectional"))
      (node (ref "SV1") (pin "29") (pinfunction "29_29") (pintype "passive"))
    )
    (net (code "88") (name "Net-(OP8-+INB)") (class "Default")
      (node (ref "OP8") (pin "5") (pinfunction "+INB_5") (pintype "bidirectional"))
      (node (ref "SV1") (pin "30") (pinfunction "30_30") (pintype "passive"))
    )
    (net (code "89") (name "Net-(OP8-+INC)") (class "Default")
      (node (ref "OP8") (pin "10") (pinfunction "+INC_10") (pintype "bidirectional"))
      (node (ref "SV1") (pin "31") (pinfunction "31_31") (pintype "passive"))
    )
    (net (code "90") (name "Net-(OP8-+IND)") (class "Default")
      (node (ref "OP8") (pin "12") (pinfunction "+IND_12") (pintype "bidirectional"))
      (node (ref "SV1") (pin "32") (pinfunction "32_32") (pintype "passive"))
    )
    (net (code "91") (name "Net-(OP8--INA)") (class "Default")
      (node (ref "OP8") (pin "2") (pinfunction "-INA_2") (pintype "bidirectional"))
      (node (ref "R1") (pin "2") (pinfunction "2_2") (pintype "passive"))
      (node (ref "R2") (pin "1") (pinfunction "1_1") (pintype "passive"))
    )
    (net (code "92") (name "Net-(OP8--INB)") (class "Default")
      (node (ref "OP8") (pin "6") (pinfunction "-INB_6") (pintype "bidirectional"))
      (node (ref "R3") (pin "2") (pinfunction "2_2") (pintype "passive"))
      (node (ref "R4") (pin "2") (pinfunction "2_2") (pintype "passive"))
    )
    (net (code "93") (name "Net-(OP8--INC)") (class "Default")
      (node (ref "OP8") (pin "9") (pinfunction "-INC_9") (pintype "bidirectional"))
      (node (ref "R7") (pin "1") (pinfunction "1_1") (pintype "passive"))
      (node (ref "R8") (pin "2") (pinfunction "2_2") (pintype "passive"))
    )
    (net (code "94") (name "Net-(OP8--IND)") (class "Default")
      (node (ref "OP8") (pin "13") (pinfunction "-IND_13") (pintype "bidirectional"))
      (node (ref "R5") (pin "2") (pinfunction "2_2") (pintype "passive"))
      (node (ref "R6") (pin "2") (pinfunction "2_2") (pintype "passive"))
    )
    (net (code "95") (name "Net-(OP8-OUTA)") (class "Default")
      (node (ref "OP8") (pin "1") (pinfunction "OUTA_1") (pintype "bidirectional"))
      (node (ref "R2") (pin "2") (pinfunction "2_2") (pintype "passive"))
      (node (ref "SV2") (pin "29") (pinfunction "29_29") (pintype "passive"))
    )
    (net (code "96") (name "Net-(OP8-OUTB)") (class "Default")
      (node (ref "OP8") (pin "7") (pinfunction "OUTB_7") (pintype "bidirectional"))
      (node (ref "R4") (pin "1") (pinfunction "1_1") (pintype "passive"))
      (node (ref "SV2") (pin "30") (pinfunction "30_30") (pintype "passive"))
    )
    (net (code "97") (name "Net-(OP8-OUTC)") (class "Default")
      (node (ref "OP8") (pin "8") (pinfunction "OUTC_8") (pintype "bidirectional"))
      (node (ref "R8") (pin "1") (pinfunction "1_1") (pintype "passive"))
      (node (ref "SV2") (pin "31") (pinfunction "31_31") (pintype "passive"))
    )
    (net (code "98") (name "Net-(OP8-OUTD)") (class "Default")
      (node (ref "OP8") (pin "14") (pinfunction "OUTD_14") (pintype "bidirectional"))
      (node (ref "R6") (pin "1") (pinfunction "1_1") (pintype "passive"))
      (node (ref "SV2") (pin "32") (pinfunction "32_32") (pintype "passive"))
    )
    (net (code "99") (name "VCC") (class "Default")
      (node (ref "C1") (pin "2") (pinfunction "2_2") (pintype "passive"))
      (node (ref "D1") (pin "A") (pinfunction "A_A") (pintype "passive"))
      (node (ref "OP1") (pin "4") (pinfunction "V+_4") (pintype "bidirectional"))
      (node (ref "OP2") (pin "4") (pinfunction "V+_4") (pintype "bidirectional"))
      (node (ref "OP3") (pin "4") (pinfunction "V+_4") (pintype "bidirectional"))
      (node (ref "OP4") (pin "4") (pinfunction "V+_4") (pintype "bidirectional"))
      (node (ref "OP5") (pin "4") (pinfunction "V+_4") (pintype "bidirectional"))
      (node (ref "OP6") (pin "4") (pinfunction "V+_4") (pintype "bidirectional"))
    )
    (net (code "100") (name "VEE") (class "Default")
      (node (ref "C2") (pin "1") (pinfunction "1_1") (pintype "passive"))
      (node (ref "D2") (pin "K") (pinfunction "K_K") (pintype "passive"))
      (node (ref "OP1") (pin "11") (pinfunction "V-_11") (pintype "bidirectional"))
      (node (ref "OP2") (pin "11") (pinfunction "V-_11") (pintype "bidirectional"))
      (node (ref "OP3") (pin "11") (pinfunction "V-_11") (pintype "bidirectional"))
      (node (ref "OP4") (pin "11") (pinfunction "V-_11") (pintype "bidirectional"))
      (node (ref "OP5") (pin "11") (pinfunction "V-_11") (pintype "bidirectional"))
      (node (ref "OP6") (pin "11") (pinfunction "V-_11") (pintype "bidirectional"))
      (node (ref "OP7") (pin "11") (pinfunction "V-_11") (pintype "bidirectional"))
      (node (ref "OP8") (pin "11") (pinfunction "V-_11") (pintype "bidirectional"))
    )
    (net (code "101") (name "unconnected-(R11-Pad2)") (class "Default")
      (node (ref "R11") (pin "2") (pinfunction "2_2") (pintype "passive"))
    )
    (net (code "102") (name "unconnected-(R15-Pad1)") (class "Default")
      (node (ref "R15") (pin "1") (pinfunction "1_1") (pintype "passive"))
    )
    (net (code "103") (name "unconnected-(SV1-Pad33)") (class "Default")
      (node (ref "SV1") (pin "33") (pinfunction "33_33") (pintype "passive"))
    )
    (net (code "104") (name "unconnected-(SV1-Pad34)") (class "Default")
      (node (ref "SV1") (pin "34") (pinfunction "34_34") (pintype "passive"))
    )
    (net (code "105") (name "unconnected-(SV1-Pad35)") (class "Default")
      (node (ref "SV1") (pin "35") (pinfunction "35_35") (pintype "passive"))
    )
    (net (code "106") (name "unconnected-(SV1-Pad36)") (class "Default")
      (node (ref "SV1") (pin "36") (pinfunction "36_36") (pintype "passive"))
    )
    (net (code "107") (name "unconnected-(SV1-Pad37)") (class "Default")
      (node (ref "SV1") (pin "37") (pinfunction "37_37") (pintype "passive"))
    )
    (net (code "108") (name "unconnected-(SV1-Pad38)") (class "Default")
      (node (ref "SV1") (pin "38") (pinfunction "38_38") (pintype "passive"))
    )
    (net (code "109") (name "unconnected-(SV1-Pad39)") (class "Default")
      (node (ref "SV1") (pin "39") (pinfunction "39_39") (pintype "passive"))
    )
    (net (code "110") (name "unconnected-(SV1-Pad40)") (class "Default")
      (node (ref "SV1") (pin "40") (pinfunction "40_40") (pintype "passive"))
    )
    (net (code "111") (name "unconnected-(SV2-Pad33)") (class "Default")
      (node (ref "SV2") (pin "33") (pinfunction "33_33") (pintype "passive"))
    )
    (net (code "112") (name "unconnected-(SV2-Pad34)") (class "Default")
      (node (ref "SV2") (pin "34") (pinfunction "34_34") (pintype "passive"))
    )
    (net (code "113") (name "unconnected-(SV2-Pad35)") (class "Default")
      (node (ref "SV2") (pin "35") (pinfunction "35_35") (pintype "passive"))
    )
    (net (code "114") (name "unconnected-(SV2-Pad36)") (class "Default")
      (node (ref "SV2") (pin "36") (pinfunction "36_36") (pintype "passive"))
    )
    (net (code "115") (name "unconnected-(SV2-Pad37)") (class "Default")
      (node (ref "SV2") (pin "37") (pinfunction "37_37") (pintype "passive"))
    )
    (net (code "116") (name "unconnected-(SV2-Pad38)") (class "Default")
      (node (ref "SV2") (pin "38") (pinfunction "38_38") (pintype "passive"))
    )
    (net (code "117") (name "unconnected-(SV2-Pad39)") (class "Default")
      (node (ref "SV2") (pin "39") (pinfunction "39_39") (pintype "passive"))
    )
    (net (code "118") (name "unconnected-(SV2-Pad40)") (class "Default")
      (node (ref "SV2") (pin "40") (pinfunction "40_40") (pintype "passive"))
    )
  )
)
